# Sensores.net
KiCad netlist of a schematic drawn in Altium Designer
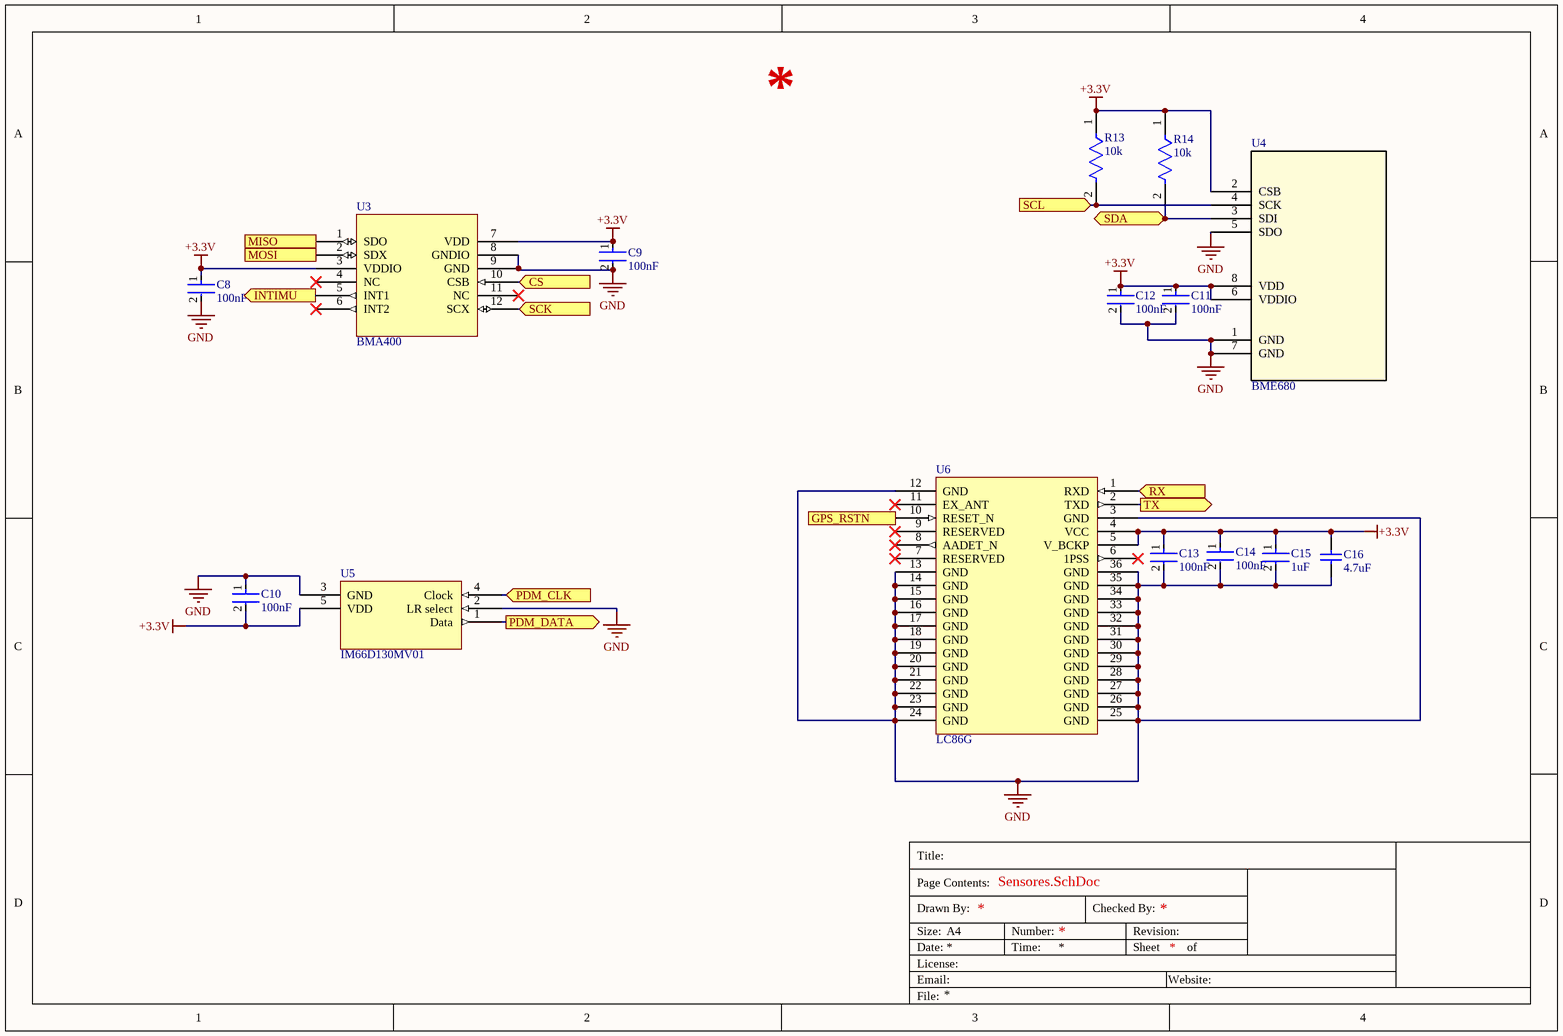
[diagram p0: Sensores.SchDoc]

(export (version "E")
  (design (tool "Eeschema 10.0.6"))
  (components
    (comp (ref "C8")
      (value "100nF")
      (footprint "FP-GCG188-0_2-IPC_B")
      (libsource (lib "Altium Content Vault") (part "02cd4be3c70576c341d710602a673aa"))
    )
    (comp (ref "C9")
      (value "100nF")
      (footprint "FP-GCG188-0_2-IPC_B")
      (libsource (lib "Altium Content Vault") (part "02cd4be3c70576c341d710602a673aa"))
    )
    (comp (ref "C10")
      (value "100nF")
      (footprint "FP-GCG188-0_2-IPC_B")
      (libsource (lib "Altium Content Vault") (part "02cd4be3c70576c341d710602a673aa"))
    )
    (comp (ref "C11")
      (value "100nF")
      (footprint "FP-GCG188-0_2-IPC_B")
      (libsource (lib "Altium Content Vault") (part "02cd4be3c70576c341d710602a673aa"))
    )
    (comp (ref "C12")
      (value "100nF")
      (footprint "FP-GCG188-0_2-IPC_B")
      (libsource (lib "Altium Content Vault") (part "02cd4be3c70576c341d710602a673aa"))
    )
    (comp (ref "C13")
      (value "100nF")
      (footprint "FP-GCG188-0_2-IPC_B")
      (libsource (lib "Altium Content Vault") (part "02cd4be3c70576c341d710602a673aa"))
    )
    (comp (ref "C14")
      (value "100nF")
      (footprint "FP-GCG188-0_2-IPC_B")
      (libsource (lib "Altium Content Vault") (part "02cd4be3c70576c341d710602a673aa"))
    )
    (comp (ref "C15")
      (value "1uF")
      (footprint "FP-CL10-IPC_C")
      (description "Cap Ceramic 1uF 16V X7R ±10% Pad SMD 0603 +125°C T/R")
      (fields (field (name "TOLERANCE") "10%"))
      (libsource (lib "Altium Content Vault") (part "b4654b650e69147ec39a6b967a45e02"))
    )
    (comp (ref "C16")
      (value "4.7uF")
      (footprint "CAPC2014X150X70ML20")
      (fields
        (field (name "PART NUMBER") "TACR475M010RTA")
        (field (name "MANUFACTURER") "AVX Interconnect / Elco")
      )
      (libsource (lib "Altium Content Vault") (part "CAP"))
    )
    (comp (ref "R13")
      (value "10k")
      (footprint "FP-CRCW0603-HPe3-MFG")
      (description "RES SMD 10K OHM 1% 1/3W 0603")
      (fields (field (name "TOLERANCE") "1%"))
      (libsource (lib "Altium Content Vault") (part "1029c3af85768c4190bb7ad29bc67b5"))
    )
    (comp (ref "R14")
      (value "10k")
      (footprint "FP-CRCW0603-HPe3-MFG")
      (description "RES SMD 10K OHM 1% 1/3W 0603")
      (fields (field (name "TOLERANCE") "1%"))
      (libsource (lib "Altium Content Vault") (part "1029c3af85768c4190bb7ad29bc67b5"))
    )
    (comp (ref "U3") (value "BMA400") (footprint "LGA-12") (libsource (lib "DEOP2026") (part "BMA400")))
    (comp (ref "U4")
      (value "BME680")
      (footprint "LGA8_BME680_BOS")
      (description "Description")
      (fields (field (name "COPYRIGHT") "Copyright (C) 2025 Ultra Librarian. All rights reserved."))
      (libsource (lib "BME680") (part "BME680"))
    )
    (comp (ref "U5")
      (value "IM66D130MV01")
      (footprint "IFX-PG-TLGA-5-8")
      (libsource (lib "DEOP2026") (part "IM66D130MV01"))
    )
    (comp (ref "U6") (value "LC86G") (footprint "LD86G") (libsource (lib "DEOP2026") (part "LC86G")))
  )
  (nets
    (net (code "1") (name "+3.3V") (class "Default")
      (node (ref "C10") (pin "2") (pinfunction "2_2") (pintype "passive"))
      (node (ref "C11") (pin "1") (pinfunction "1_1") (pintype "passive"))
      (node (ref "C12") (pin "1") (pinfunction "1_1") (pintype "passive"))
      (node (ref "C13") (pin "1") (pinfunction "1_1") (pintype "passive"))
      (node (ref "C14") (pin "1") (pinfunction "1_1") (pintype "passive"))
      (node (ref "C15") (pin "1") (pinfunction "1_1") (pintype "passive"))
      (node (ref "C16") (pin "2") (pinfunction "2_2") (pintype "passive"))
      (node (ref "C8") (pin "1") (pinfunction "1_1") (pintype "passive"))
      (node (ref "C9") (pin "1") (pinfunction "1_1") (pintype "passive"))
      (node (ref "R13") (pin "1") (pinfunction "1_1") (pintype "passive"))
      (node (ref "R14") (pin "1") (pinfunction "1_1") (pintype "passive"))
      (node (ref "U3") (pin "3") (pinfunction "VDDIO_3") (pintype "power_in"))
      (node (ref "U3") (pin "7") (pinfunction "VDD_7") (pintype "power_in"))
      (node (ref "U4") (pin "2") (pinfunction "CSB_2") (pintype "passive"))
      (node (ref "U4") (pin "6") (pinfunction "VDDIO_6") (pintype "passive"))
      (node (ref "U4") (pin "8") (pinfunction "VDD_8") (pintype "passive"))
      (node (ref "U5") (pin "5") (pinfunction "VDD_5") (pintype "power_in"))
      (node (ref "U6") (pin "4") (pinfunction "VCC_4") (pintype "power_in"))
      (node (ref "U6") (pin "5") (pinfunction "V_BCKP_5") (pintype "power_in"))
    )
    (net (code "2") (name "/CS") (class "Default")
      (node (ref "U3") (pin "10") (pinfunction "CSB_10") (pintype "input"))
    )
    (net (code "3") (name "/GPS_RSTN") (class "Default")
      (node (ref "U6") (pin "10") (pinfunction "RESET_N_10") (pintype "input"))
    )
    (net (code "4") (name "/INTIMU") (class "Default")
      (node (ref "U3") (pin "5") (pinfunction "INT1_5") (pintype "output"))
    )
    (net (code "5") (name "/MISO") (class "Default")
      (node (ref "U3") (pin "1") (pinfunction "SDO_1") (pintype "bidirectional"))
    )
    (net (code "6") (name "/MOSI") (class "Default")
      (node (ref "U3") (pin "2") (pinfunction "SDX_2") (pintype "bidirectional"))
    )
    (net (code "7") (name "/PDM_CLK") (class "Default")
      (node (ref "U5") (pin "4") (pinfunction "Clock_4") (pintype "input"))
    )
    (net (code "8") (name "/PDM_DATA") (class "Default")
      (node (ref "U5") (pin "1") (pinfunction "Data_1") (pintype "output"))
    )
    (net (code "9") (name "/RX") (class "Default")
      (node (ref "U6") (pin "1") (pinfunction "RXD_1") (pintype "input"))
    )
    (net (code "10") (name "/SCK") (class "Default")
      (node (ref "U3") (pin "12") (pinfunction "SCX_12") (pintype "bidirectional"))
    )
    (net (code "11") (name "/SCL") (class "Default")
      (node (ref "R13") (pin "2") (pinfunction "2_2") (pintype "passive"))
      (node (ref "U4") (pin "4") (pinfunction "SCK_4") (pintype "passive"))
    )
    (net (code "12") (name "/SDA") (class "Default")
      (node (ref "R14") (pin "2") (pinfunction "2_2") (pintype "passive"))
      (node (ref "U4") (pin "3") (pinfunction "SDI_3") (pintype "passive"))
    )
    (net (code "13") (name "/TX") (class "Default")
      (node (ref "U6") (pin "2") (pinfunction "TXD_2") (pintype "output"))
    )
    (net (code "14") (name "GND") (class "Default")
      (node (ref "C10") (pin "1") (pinfunction "1_1") (pintype "passive"))
      (node (ref "C11") (pin "2") (pinfunction "2_2") (pintype "passive"))
      (node (ref "C12") (pin "2") (pinfunction "2_2") (pintype "passive"))
      (node (ref "C13") (pin "2") (pinfunction "2_2") (pintype "passive"))
      (node (ref "C14") (pin "2") (pinfunction "2_2") (pintype "passive"))
      (node (ref "C15") (pin "2") (pinfunction "2_2") (pintype "passive"))
      (node (ref "C16") (pin "1") (pinfunction "1_1") (pintype "passive"))
      (node (ref "C8") (pin "2") (pinfunction "2_2") (pintype "passive"))
      (node (ref "C9") (pin "2") (pinfunction "2_2") (pintype "passive"))
      (node (ref "U3") (pin "8") (pinfunction "GNDIO_8") (pintype "power_in"))
      (node (ref "U3") (pin "9") (pinfunction "GND_9") (pintype "power_in"))
      (node (ref "U4") (pin "1") (pinfunction "GND_1") (pintype "passive"))
      (node (ref "U4") (pin "5") (pinfunction "SDO_5") (pintype "passive"))
      (node (ref "U4") (pin "7") (pinfunction "GND_7") (pintype "passive"))
      (node (ref "U5") (pin "2") (pinfunction "LR_select_2") (pintype "input"))
      (node (ref "U5") (pin "3") (pinfunction "GND_3") (pintype "power_in"))
      (node (ref "U6") (pin "12") (pinfunction "GND_12") (pintype "power_in"))
      (node (ref "U6") (pin "13") (pinfunction "GND_13") (pintype "power_in"))
      (node (ref "U6") (pin "14") (pinfunction "GND_14") (pintype "power_in"))
      (node (ref "U6") (pin "15") (pinfunction "GND_15") (pintype "power_in"))
      (node (ref "U6") (pin "16") (pinfunction "GND_16") (pintype "power_in"))
      (node (ref "U6") (pin "17") (pinfunction "GND_17") (pintype "power_in"))
      (node (ref "U6") (pin "18") (pinfunction "GND_18") (pintype "power_in"))
      (node (ref "U6") (pin "19") (pinfunction "GND_19") (pintype "power_in"))
      (node (ref "U6") (pin "20") (pinfunction "GND_20") (pintype "power_in"))
      (node (ref "U6") (pin "21") (pinfunction "GND_21") (pintype "power_in"))
      (node (ref "U6") (pin "22") (pinfunction "GND_22") (pintype "power_in"))
      (node (ref "U6") (pin "23") (pinfunction "GND_23") (pintype "power_in"))
      (node (ref "U6") (pin "24") (pinfunction "GND_24") (pintype "power_in"))
      (node (ref "U6") (pin "25") (pinfunction "GND_25") (pintype "power_in"))
      (node (ref "U6") (pin "26") (pinfunction "GND_26") (pintype "power_in"))
      (node (ref "U6") (pin "27") (pinfunction "GND_27") (pintype "power_in"))
      (node (ref "U6") (pin "28") (pinfunction "GND_28") (pintype "power_in"))
      (node (ref "U6") (pin "29") (pinfunction "GND_29") (pintype "power_in"))
      (node (ref "U6") (pin "3") (pinfunction "GND_3") (pintype "power_in"))
      (node (ref "U6") (pin "30") (pinfunction "GND_30") (pintype "power_in"))
      (node (ref "U6") (pin "31") (pinfunction "GND_31") (pintype "power_in"))
      (node (ref "U6") (pin "32") (pinfunction "GND_32") (pintype "power_in"))
      (node (ref "U6") (pin "33") (pinfunction "GND_33") (pintype "power_in"))
      (node (ref "U6") (pin "34") (pinfunction "GND_34") (pintype "power_in"))
      (node (ref "U6") (pin "35") (pinfunction "GND_35") (pintype "power_in"))
      (node (ref "U6") (pin "36") (pinfunction "GND_36") (pintype "power_in"))
    )
    (net (code "15") (name "unconnected-(U3-INT2-Pad6)") (class "Default")
      (node (ref "U3") (pin "6") (pinfunction "INT2_6") (pintype "output+no_connect"))
    )
    (net (code "16") (name "unconnected-(U3-NC-Pad4)") (class "Default")
      (node (ref "U3") (pin "4") (pinfunction "NC_4") (pintype "passive+no_connect"))
    )
    (net (code "17") (name "unconnected-(U3-NC-Pad11)") (class "Default")
      (node (ref "U3") (pin "11") (pinfunction "NC_11") (pintype "passive+no_connect"))
    )
    (net (code "18") (name "unconnected-(U6-1PSS-Pad6)") (class "Default")
      (node (ref "U6") (pin "6") (pinfunction "1PSS_6") (pintype "output+no_connect"))
    )
    (net (code "19") (name "unconnected-(U6-AADET_N-Pad8)") (class "Default")
      (node (ref "U6") (pin "8") (pinfunction "AADET_N_8") (pintype "output+no_connect"))
    )
    (net (code "20") (name "unconnected-(U6-EX_ANT-Pad11)") (class "Default")
      (node (ref "U6") (pin "11") (pinfunction "EX_ANT_11") (pintype "passive+no_connect"))
    )
    (net (code "21") (name "unconnected-(U6-RESERVED-Pad7)") (class "Default")
      (node (ref "U6") (pin "7") (pinfunction "RESERVED_7") (pintype "passive+no_connect"))
    )
    (net (code "22") (name "unconnected-(U6-RESERVED-Pad9)") (class "Default")
      (node (ref "U6") (pin "9") (pinfunction "RESERVED_9") (pintype "passive+no_connect"))
    )
  )
)
